# mwscoretransponder2013.net
KiCad netlist of a schematic drawn in EAGLE
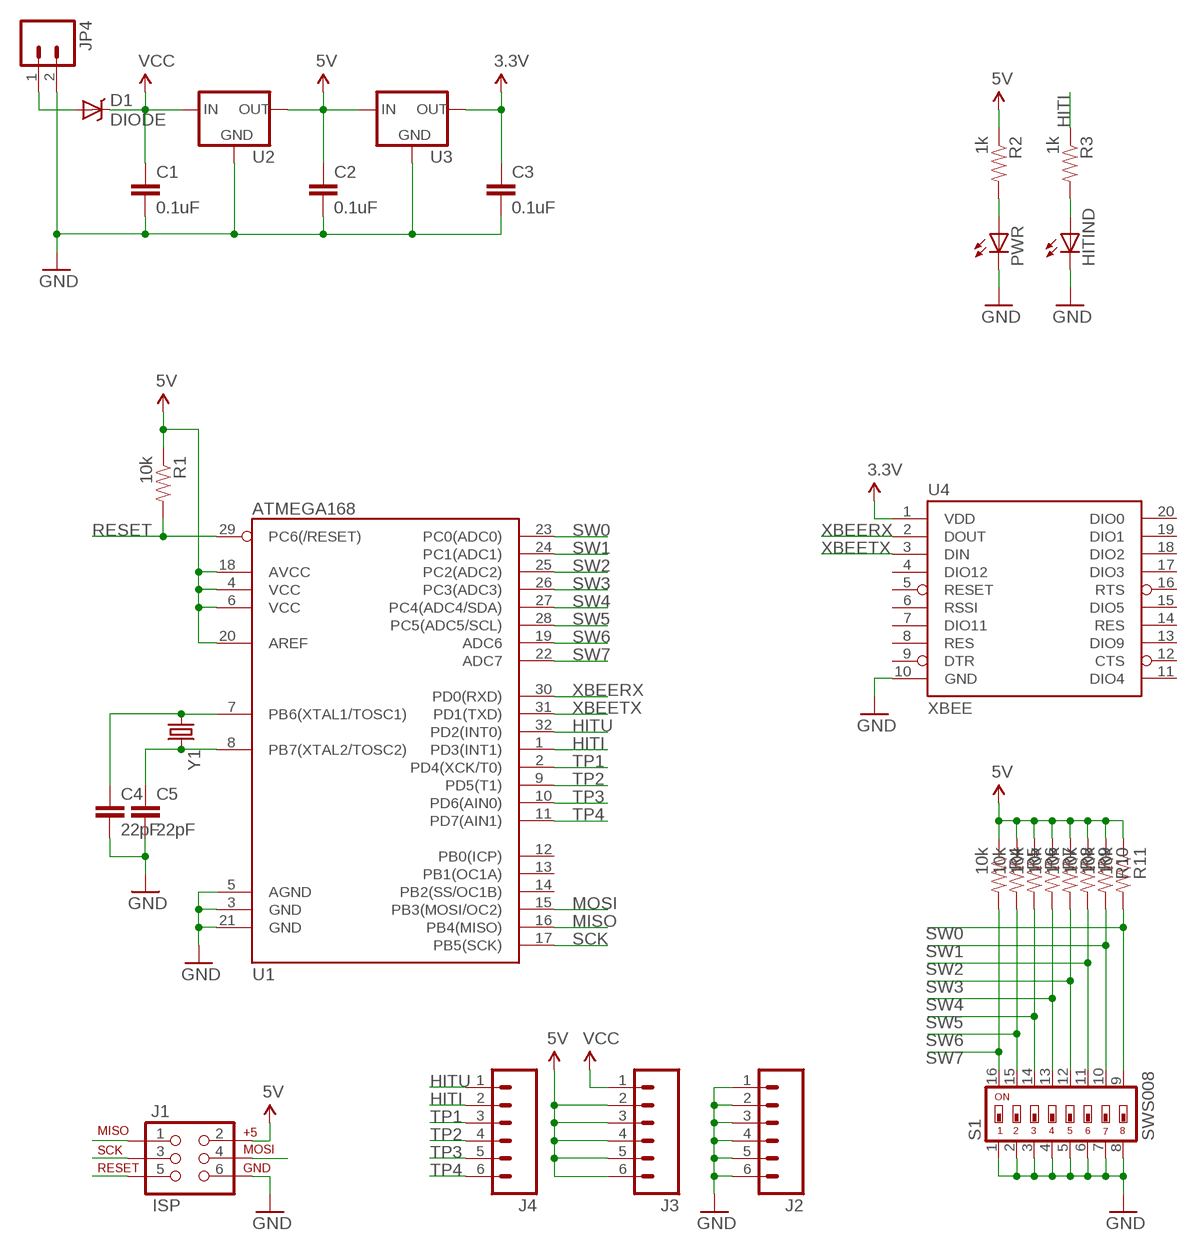
[diagram p0: schematic, sheet 1]

(export (version "E")
  (design (tool "Eeschema 10.0.6"))
  (components
    (comp (ref "C1")
      (value "0.1uF")
      (footprint "eagle-import:0603-CAP")
      (libsource (lib "eagle-import") (part "CAP0603-CAP"))
    )
    (comp (ref "C2")
      (value "0.1uF")
      (footprint "eagle-import:0603-CAP")
      (libsource (lib "eagle-import") (part "CAP0603-CAP"))
    )
    (comp (ref "C3")
      (value "0.1uF")
      (footprint "eagle-import:0603-CAP")
      (libsource (lib "eagle-import") (part "CAP0603-CAP"))
    )
    (comp (ref "C4")
      (value "22pF")
      (footprint "eagle-import:0603-CAP")
      (libsource (lib "eagle-import") (part "CAP0603-CAP"))
    )
    (comp (ref "C5")
      (value "22pF")
      (footprint "eagle-import:0603-CAP")
      (libsource (lib "eagle-import") (part "CAP0603-CAP"))
    )
    (comp (ref "D1")
      (value "DIODE")
      (footprint "eagle-import:SMA-DIODE")
      (libsource (lib "eagle-import") (part "DIODE-SCHOTTKY_"))
    )
    (comp (ref "HITIND")
      (value "LED0603")
      (footprint "eagle-import:LED-0603")
      (libsource (lib "eagle-import") (part "LED0603"))
    )
    (comp (ref "J1")
      (value "ISP")
      (footprint "eagle-import:2X3")
      (libsource (lib "eagle-import") (part "AVR_SPI_PRG_6PTH"))
    )
    (comp (ref "J2")
      (value "M06SIP")
      (footprint "eagle-import:1X06")
      (libsource (lib "eagle-import") (part "M06SIP"))
    )
    (comp (ref "J3")
      (value "M06SIP")
      (footprint "eagle-import:1X06")
      (libsource (lib "eagle-import") (part "M06SIP"))
    )
    (comp (ref "J4")
      (value "M06SIP")
      (footprint "eagle-import:1X06")
      (libsource (lib "eagle-import") (part "M06SIP"))
    )
    (comp (ref "JP4")
      (value "M023.5MM_LOCK")
      (footprint "eagle-import:SCREWTERMINAL-3.5MM-2_LOCK")
      (libsource (lib "eagle-import") (part "M023.5MM_LOCK"))
    )
    (comp (ref "PWR")
      (value "LED0603")
      (footprint "eagle-import:LED-0603")
      (libsource (lib "eagle-import") (part "LED0603"))
    )
    (comp (ref "R1")
      (value "10k")
      (footprint "eagle-import:0603-RES")
      (libsource (lib "eagle-import") (part "RESISTOR0603-RES"))
    )
    (comp (ref "R2")
      (value "1k")
      (footprint "eagle-import:0603-RES")
      (libsource (lib "eagle-import") (part "RESISTOR0603-RES"))
    )
    (comp (ref "R3")
      (value "1k")
      (footprint "eagle-import:0603-RES")
      (libsource (lib "eagle-import") (part "RESISTOR0603-RES"))
    )
    (comp (ref "R4")
      (value "10k")
      (footprint "eagle-import:0603-RES")
      (libsource (lib "eagle-import") (part "RESISTOR0603-RES"))
    )
    (comp (ref "R5")
      (value "10k")
      (footprint "eagle-import:0603-RES")
      (libsource (lib "eagle-import") (part "RESISTOR0603-RES"))
    )
    (comp (ref "R6")
      (value "10k")
      (footprint "eagle-import:0603-RES")
      (libsource (lib "eagle-import") (part "RESISTOR0603-RES"))
    )
    (comp (ref "R7")
      (value "10k")
      (footprint "eagle-import:0603-RES")
      (libsource (lib "eagle-import") (part "RESISTOR0603-RES"))
    )
    (comp (ref "R8")
      (value "10k")
      (footprint "eagle-import:0603-RES")
      (libsource (lib "eagle-import") (part "RESISTOR0603-RES"))
    )
    (comp (ref "R9")
      (value "10k")
      (footprint "eagle-import:0603-RES")
      (libsource (lib "eagle-import") (part "RESISTOR0603-RES"))
    )
    (comp (ref "R10")
      (value "10k")
      (footprint "eagle-import:0603-RES")
      (libsource (lib "eagle-import") (part "RESISTOR0603-RES"))
    )
    (comp (ref "R11")
      (value "10k")
      (footprint "eagle-import:0603-RES")
      (libsource (lib "eagle-import") (part "RESISTOR0603-RES"))
    )
    (comp (ref "S1")
      (value "SWS008")
      (footprint "eagle-import:SMS-008")
      (libsource (lib "eagle-import") (part "SWS008"))
    )
    (comp (ref "U1")
      (value "ATMEGA168")
      (footprint "eagle-import:TQFP32-08")
      (libsource (lib "eagle-import") (part "ATMEGA168"))
    )
    (comp (ref "U2")
      (value "V_REG_MIC2920")
      (footprint "eagle-import:SOT223")
      (libsource (lib "eagle-import") (part "V_REG_MIC2920"))
    )
    (comp (ref "U3")
      (value "V_REG_MIC2920")
      (footprint "eagle-import:SOT223")
      (libsource (lib "eagle-import") (part "V_REG_MIC2920"))
    )
    (comp (ref "U4")
      (value "XBEE")
      (footprint "eagle-import:XBEE-SMD")
      (libsource (lib "eagle-import") (part "XBEE-1B3"))
    )
    (comp (ref "Y1")
      (value "CRYSTAL5X3")
      (footprint "eagle-import:CRYSTAL-SMD-5X3")
      (libsource (lib "eagle-import") (part "CRYSTAL5X3"))
    )
  )
  (nets
    (net (code "1") (name "/HITI") (class "Default")
      (node (ref "J4") (pin "2") (pinfunction "2_2") (pintype "passive"))
      (node (ref "R3") (pin "1") (pinfunction "1_1") (pintype "passive"))
      (node (ref "U1") (pin "1") (pinfunction "PD3(INT1)_1") (pintype "bidirectional"))
    )
    (net (code "2") (name "/HITU") (class "Default")
      (node (ref "J4") (pin "1") (pinfunction "1_1") (pintype "passive"))
      (node (ref "U1") (pin "32") (pinfunction "PD2(INT0)_32") (pintype "bidirectional"))
    )
    (net (code "3") (name "/MISO") (class "Default")
      (node (ref "J1") (pin "1") (pinfunction "1_1") (pintype "passive"))
      (node (ref "U1") (pin "16") (pinfunction "PB4(MISO)_16") (pintype "bidirectional"))
    )
    (net (code "4") (name "/MOSI") (class "Default")
      (node (ref "J1") (pin "4") (pinfunction "4_4") (pintype "passive"))
      (node (ref "U1") (pin "15") (pinfunction "PB3(MOSI/OC2)_15") (pintype "bidirectional"))
    )
    (net (code "5") (name "/RESET") (class "Default")
      (node (ref "J1") (pin "5") (pinfunction "5_5") (pintype "passive"))
      (node (ref "R1") (pin "2") (pinfunction "2_2") (pintype "passive"))
      (node (ref "U1") (pin "29") (pinfunction "PC6(/RESET)_29") (pintype "bidirectional"))
    )
    (net (code "6") (name "/SCK") (class "Default")
      (node (ref "J1") (pin "3") (pinfunction "3_3") (pintype "passive"))
      (node (ref "U1") (pin "17") (pinfunction "PB5(SCK)_17") (pintype "bidirectional"))
    )
    (net (code "7") (name "/SW0") (class "Default")
      (node (ref "R11") (pin "2") (pinfunction "2_2") (pintype "passive"))
      (node (ref "S1") (pin "9") (pinfunction "9_9") (pintype "passive"))
      (node (ref "U1") (pin "23") (pinfunction "PC0(ADC0)_23") (pintype "bidirectional"))
    )
    (net (code "8") (name "/SW1") (class "Default")
      (node (ref "R10") (pin "2") (pinfunction "2_2") (pintype "passive"))
      (node (ref "S1") (pin "10") (pinfunction "10_10") (pintype "passive"))
      (node (ref "U1") (pin "24") (pinfunction "PC1(ADC1)_24") (pintype "bidirectional"))
    )
    (net (code "9") (name "/SW2") (class "Default")
      (node (ref "R9") (pin "2") (pinfunction "2_2") (pintype "passive"))
      (node (ref "S1") (pin "11") (pinfunction "11_11") (pintype "passive"))
      (node (ref "U1") (pin "25") (pinfunction "PC2(ADC2)_25") (pintype "bidirectional"))
    )
    (net (code "10") (name "/SW3") (class "Default")
      (node (ref "R8") (pin "2") (pinfunction "2_2") (pintype "passive"))
      (node (ref "S1") (pin "12") (pinfunction "12_12") (pintype "passive"))
      (node (ref "U1") (pin "26") (pinfunction "PC3(ADC3)_26") (pintype "bidirectional"))
    )
    (net (code "11") (name "/SW4") (class "Default")
      (node (ref "R7") (pin "2") (pinfunction "2_2") (pintype "passive"))
      (node (ref "S1") (pin "13") (pinfunction "13_13") (pintype "passive"))
      (node (ref "U1") (pin "27") (pinfunction "PC4(ADC4/SDA)_27") (pintype "bidirectional"))
    )
    (net (code "12") (name "/SW5") (class "Default")
      (node (ref "R6") (pin "2") (pinfunction "2_2") (pintype "passive"))
      (node (ref "S1") (pin "14") (pinfunction "14_14") (pintype "passive"))
      (node (ref "U1") (pin "28") (pinfunction "PC5(ADC5/SCL)_28") (pintype "bidirectional"))
    )
    (net (code "13") (name "/SW6") (class "Default")
      (node (ref "R5") (pin "2") (pinfunction "2_2") (pintype "passive"))
      (node (ref "S1") (pin "15") (pinfunction "15_15") (pintype "passive"))
      (node (ref "U1") (pin "19") (pinfunction "ADC6_19") (pintype "bidirectional"))
    )
    (net (code "14") (name "/SW7") (class "Default")
      (node (ref "R4") (pin "2") (pinfunction "2_2") (pintype "passive"))
      (node (ref "S1") (pin "16") (pinfunction "16_16") (pintype "passive"))
      (node (ref "U1") (pin "22") (pinfunction "ADC7_22") (pintype "bidirectional"))
    )
    (net (code "15") (name "/TP1") (class "Default")
      (node (ref "J4") (pin "3") (pinfunction "3_3") (pintype "passive"))
      (node (ref "U1") (pin "2") (pinfunction "PD4(XCK/T0)_2") (pintype "bidirectional"))
    )
    (net (code "16") (name "/TP2") (class "Default")
      (node (ref "J4") (pin "4") (pinfunction "4_4") (pintype "passive"))
      (node (ref "U1") (pin "9") (pinfunction "PD5(T1)_9") (pintype "bidirectional"))
    )
    (net (code "17") (name "/TP3") (class "Default")
      (node (ref "J4") (pin "5") (pinfunction "5_5") (pintype "passive"))
      (node (ref "U1") (pin "10") (pinfunction "PD6(AIN0)_10") (pintype "bidirectional"))
    )
    (net (code "18") (name "/TP4") (class "Default")
      (node (ref "J4") (pin "6") (pinfunction "6_6") (pintype "passive"))
      (node (ref "U1") (pin "11") (pinfunction "PD7(AIN1)_11") (pintype "bidirectional"))
    )
    (net (code "19") (name "/XBEERX") (class "Default")
      (node (ref "U1") (pin "30") (pinfunction "PD0(RXD)_30") (pintype "bidirectional"))
      (node (ref "U4") (pin "2") (pinfunction "DOUT_2") (pintype "output"))
    )
    (net (code "20") (name "/XBEETX") (class "Default")
      (node (ref "U1") (pin "31") (pinfunction "PD1(TXD)_31") (pintype "bidirectional"))
      (node (ref "U4") (pin "3") (pinfunction "DIN_3") (pintype "input"))
    )
    (net (code "21") (name "3.3V") (class "Default")
      (node (ref "C3") (pin "1") (pinfunction "1_1") (pintype "passive"))
      (node (ref "U3") (pin "3") (pinfunction "OUT_3") (pintype "output"))
      (node (ref "U4") (pin "1") (pinfunction "VDD_1") (pintype "power_in"))
    )
    (net (code "22") (name "5V") (class "Default")
      (node (ref "C2") (pin "1") (pinfunction "1_1") (pintype "passive"))
      (node (ref "J1") (pin "2") (pinfunction "2_2") (pintype "passive"))
      (node (ref "J3") (pin "2") (pinfunction "2_2") (pintype "passive"))
      (node (ref "J3") (pin "3") (pinfunction "3_3") (pintype "passive"))
      (node (ref "J3") (pin "4") (pinfunction "4_4") (pintype "passive"))
      (node (ref "J3") (pin "5") (pinfunction "5_5") (pintype "passive"))
      (node (ref "J3") (pin "6") (pinfunction "6_6") (pintype "passive"))
      (node (ref "R1") (pin "1") (pinfunction "1_1") (pintype "passive"))
      (node (ref "R10") (pin "1") (pinfunction "1_1") (pintype "passive"))
      (node (ref "R11") (pin "1") (pinfunction "1_1") (pintype "passive"))
      (node (ref "R2") (pin "1") (pinfunction "1_1") (pintype "passive"))
      (node (ref "R4") (pin "1") (pinfunction "1_1") (pintype "passive"))
      (node (ref "R5") (pin "1") (pinfunction "1_1") (pintype "passive"))
      (node (ref "R6") (pin "1") (pinfunction "1_1") (pintype "passive"))
      (node (ref "R7") (pin "1") (pinfunction "1_1") (pintype "passive"))
      (node (ref "R8") (pin "1") (pinfunction "1_1") (pintype "passive"))
      (node (ref "R9") (pin "1") (pinfunction "1_1") (pintype "passive"))
      (node (ref "U1") (pin "18") (pinfunction "AVCC_18") (pintype "bidirectional"))
      (node (ref "U1") (pin "20") (pinfunction "AREF_20") (pintype "bidirectional"))
      (node (ref "U1") (pin "4") (pinfunction "VCC_4") (pintype "bidirectional"))
      (node (ref "U1") (pin "6") (pinfunction "VCC_6") (pintype "bidirectional"))
      (node (ref "U2") (pin "3") (pinfunction "OUT_3") (pintype "output"))
      (node (ref "U3") (pin "1") (pinfunction "IN_1") (pintype "input"))
    )
    (net (code "23") (name "GND") (class "Default")
      (node (ref "C1") (pin "2") (pinfunction "2_2") (pintype "passive"))
      (node (ref "C2") (pin "2") (pinfunction "2_2") (pintype "passive"))
      (node (ref "C3") (pin "2") (pinfunction "2_2") (pintype "passive"))
      (node (ref "C4") (pin "2") (pinfunction "2_2") (pintype "passive"))
      (node (ref "C5") (pin "2") (pinfunction "2_2") (pintype "passive"))
      (node (ref "HITIND") (pin "C") (pinfunction "C_C") (pintype "passive"))
      (node (ref "J1") (pin "6") (pinfunction "6_6") (pintype "passive"))
      (node (ref "J2") (pin "1") (pinfunction "1_1") (pintype "passive"))
      (node (ref "J2") (pin "2") (pinfunction "2_2") (pintype "passive"))
      (node (ref "J2") (pin "3") (pinfunction "3_3") (pintype "passive"))
      (node (ref "J2") (pin "4") (pinfunction "4_4") (pintype "passive"))
      (node (ref "J2") (pin "5") (pinfunction "5_5") (pintype "passive"))
      (node (ref "J2") (pin "6") (pinfunction "6_6") (pintype "passive"))
      (node (ref "JP4") (pin "2") (pinfunction "2_2") (pintype "passive"))
      (node (ref "PWR") (pin "C") (pinfunction "C_C") (pintype "passive"))
      (node (ref "S1") (pin "1") (pinfunction "1_1") (pintype "passive"))
      (node (ref "S1") (pin "2") (pinfunction "2_2") (pintype "passive"))
      (node (ref "S1") (pin "3") (pinfunction "3_3") (pintype "passive"))
      (node (ref "S1") (pin "4") (pinfunction "4_4") (pintype "passive"))
      (node (ref "S1") (pin "5") (pinfunction "5_5") (pintype "passive"))
      (node (ref "S1") (pin "6") (pinfunction "6_6") (pintype "passive"))
      (node (ref "S1") (pin "7") (pinfunction "7_7") (pintype "passive"))
      (node (ref "S1") (pin "8") (pinfunction "8_8") (pintype "passive"))
      (node (ref "U1") (pin "21") (pinfunction "GND_21") (pintype "bidirectional"))
      (node (ref "U1") (pin "3") (pinfunction "GND_3") (pintype "bidirectional"))
      (node (ref "U1") (pin "5") (pinfunction "AGND_5") (pintype "bidirectional"))
      (node (ref "U2") (pin "2") (pinfunction "GND_2") (pintype "input"))
      (node (ref "U3") (pin "2") (pinfunction "GND_2") (pintype "input"))
      (node (ref "U4") (pin "10") (pinfunction "GND_10") (pintype "power_in"))
    )
    (net (code "24") (name "Net-(D1-PadA)") (class "Default")
      (node (ref "D1") (pin "A") (pinfunction "A_A") (pintype "passive"))
      (node (ref "JP4") (pin "1") (pinfunction "1_1") (pintype "passive"))
    )
    (net (code "25") (name "Net-(HITIND-PadA)") (class "Default")
      (node (ref "HITIND") (pin "A") (pinfunction "A_A") (pintype "passive"))
      (node (ref "R3") (pin "2") (pinfunction "2_2") (pintype "passive"))
    )
    (net (code "26") (name "Net-(PWR-PadA)") (class "Default")
      (node (ref "PWR") (pin "A") (pinfunction "A_A") (pintype "passive"))
      (node (ref "R2") (pin "2") (pinfunction "2_2") (pintype "passive"))
    )
    (net (code "27") (name "Net-(U1-PB6(XTAL1{slash}TOSC1))") (class "Default")
      (node (ref "C4") (pin "1") (pinfunction "1_1") (pintype "passive"))
      (node (ref "U1") (pin "7") (pinfunction "PB6(XTAL1/TOSC1)_7") (pintype "bidirectional"))
      (node (ref "Y1") (pin "1") (pinfunction "1_1") (pintype "passive"))
    )
    (net (code "28") (name "Net-(U1-PB7(XTAL2{slash}TOSC2))") (class "Default")
      (node (ref "C5") (pin "1") (pinfunction "1_1") (pintype "passive"))
      (node (ref "U1") (pin "8") (pinfunction "PB7(XTAL2/TOSC2)_8") (pintype "bidirectional"))
      (node (ref "Y1") (pin "3") (pinfunction "2_3") (pintype "passive"))
    )
    (net (code "29") (name "VCC") (class "Default")
      (node (ref "C1") (pin "1") (pinfunction "1_1") (pintype "passive"))
      (node (ref "D1") (pin "C") (pinfunction "C_C") (pintype "passive"))
      (node (ref "J3") (pin "1") (pinfunction "1_1") (pintype "passive"))
      (node (ref "U2") (pin "1") (pinfunction "IN_1") (pintype "input"))
    )
    (net (code "30") (name "unconnected-(U1-PB0(ICP)-Pad12)") (class "Default")
      (node (ref "U1") (pin "12") (pinfunction "PB0(ICP)_12") (pintype "bidirectional"))
    )
    (net (code "31") (name "unconnected-(U1-PB1(OC1A)-Pad13)") (class "Default")
      (node (ref "U1") (pin "13") (pinfunction "PB1(OC1A)_13") (pintype "bidirectional"))
    )
    (net (code "32") (name "unconnected-(U1-PB2(SS{slash}OC1B)-Pad14)") (class "Default")
      (node (ref "U1") (pin "14") (pinfunction "PB2(SS/OC1B)_14") (pintype "bidirectional"))
    )
    (net (code "33") (name "unconnected-(U4-CTS-Pad12)") (class "Default")
      (node (ref "U4") (pin "12") (pinfunction "CTS_12") (pintype "output"))
    )
    (net (code "34") (name "unconnected-(U4-DIO0-Pad20)") (class "Default")
      (node (ref "U4") (pin "20") (pinfunction "DIO0_20") (pintype "bidirectional"))
    )
    (net (code "35") (name "unconnected-(U4-DIO1-Pad19)") (class "Default")
      (node (ref "U4") (pin "19") (pinfunction "DIO1_19") (pintype "bidirectional"))
    )
    (net (code "36") (name "unconnected-(U4-DIO2-Pad18)") (class "Default")
      (node (ref "U4") (pin "18") (pinfunction "DIO2_18") (pintype "bidirectional"))
    )
    (net (code "37") (name "unconnected-(U4-DIO3-Pad17)") (class "Default")
      (node (ref "U4") (pin "17") (pinfunction "DIO3_17") (pintype "bidirectional"))
    )
    (net (code "38") (name "unconnected-(U4-DIO4-Pad11)") (class "Default")
      (node (ref "U4") (pin "11") (pinfunction "DIO4_11") (pintype "bidirectional"))
    )
    (net (code "39") (name "unconnected-(U4-DIO5-Pad15)") (class "Default")
      (node (ref "U4") (pin "15") (pinfunction "DIO5_15") (pintype "bidirectional"))
    )
    (net (code "40") (name "unconnected-(U4-DIO9-Pad13)") (class "Default")
      (node (ref "U4") (pin "13") (pinfunction "DIO9_13") (pintype "bidirectional"))
    )
    (net (code "41") (name "unconnected-(U4-DIO11-Pad7)") (class "Default")
      (node (ref "U4") (pin "7") (pinfunction "DIO11_7") (pintype "bidirectional"))
    )
    (net (code "42") (name "unconnected-(U4-DIO12-Pad4)") (class "Default")
      (node (ref "U4") (pin "4") (pinfunction "DIO12_4") (pintype "bidirectional"))
    )
    (net (code "43") (name "unconnected-(U4-DTR-Pad9)") (class "Default")
      (node (ref "U4") (pin "9") (pinfunction "DTR_9") (pintype "bidirectional"))
    )
    (net (code "44") (name "unconnected-(U4-RES-Pad8)") (class "Default")
      (node (ref "U4") (pin "8") (pinfunction "RES_8") (pintype "bidirectional"))
    )
    (net (code "45") (name "unconnected-(U4-RES-Pad14)") (class "Default")
      (node (ref "U4") (pin "14") (pinfunction "RES_14") (pintype "bidirectional"))
    )
    (net (code "46") (name "unconnected-(U4-RESET-Pad5)") (class "Default")
      (node (ref "U4") (pin "5") (pinfunction "RESET_5") (pintype "input"))
    )
    (net (code "47") (name "unconnected-(U4-RSSI-Pad6)") (class "Default")
      (node (ref "U4") (pin "6") (pinfunction "RSSI_6") (pintype "bidirectional"))
    )
    (net (code "48") (name "unconnected-(U4-RTS-Pad16)") (class "Default")
      (node (ref "U4") (pin "16") (pinfunction "RTS_16") (pintype "input"))
    )
  )
)
